# R3-URC18-4-006-001.net
KiCad netlist of a schematic drawn in EAGLE
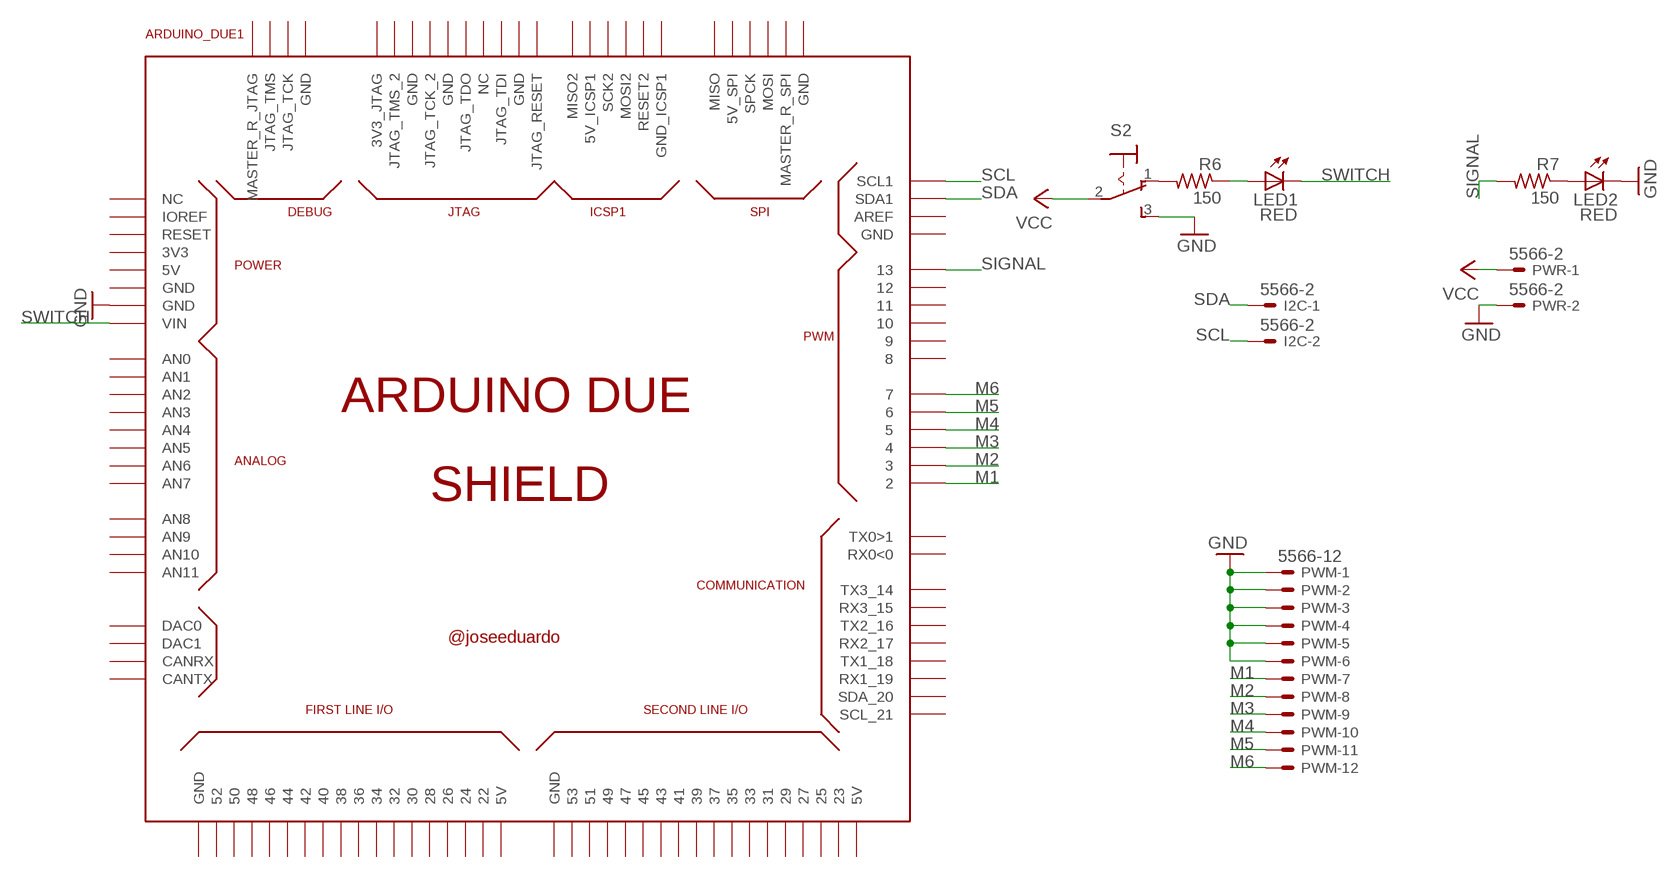
[diagram p0: schematic, sheet 1]

(export (version "E")
  (design (tool "Eeschema 10.0.6"))
  (components
    (comp (ref "ARDUINO_DUE1")
      (value "ARDUINO_DUE_SHIELD")
      (footprint "eagle-import:ARDUINO_DUE_SHIELD")
      (libsource (lib "eagle-import") (part "ARDUINO_DUE_SHIELD"))
    )
    (comp (ref "I2C")
      (value "5566-2")
      (footprint "eagle-import:5566-2")
      (libsource (lib "eagle-import") (part "5566-2"))
    )
    (comp (ref "LED1")
      (value "RED")
      (footprint "eagle-import:LED5MM")
      (libsource (lib "eagle-import") (part "LED5MM"))
    )
    (comp (ref "LED2")
      (value "RED")
      (footprint "eagle-import:LED5MM")
      (libsource (lib "eagle-import") (part "LED5MM"))
    )
    (comp (ref "PWM")
      (value "5566-12")
      (footprint "eagle-import:5566-12")
      (libsource (lib "eagle-import") (part "5566-12"))
    )
    (comp (ref "PWR")
      (value "5566-2")
      (footprint "eagle-import:5566-2")
      (libsource (lib "eagle-import") (part "5566-2"))
    )
    (comp (ref "R6")
      (value "150")
      (footprint "eagle-import:0207_10")
      (libsource (lib "eagle-import") (part "R-US_0207/10"))
    )
    (comp (ref "R7")
      (value "150")
      (footprint "eagle-import:0207_10")
      (libsource (lib "eagle-import") (part "R-US_0207/10"))
    )
    (comp (ref "S2")
      (value "M9040P")
      (footprint "eagle-import:M9040P")
      (libsource (lib "eagle-import") (part "M9040P"))
    )
  )
  (nets
    (net (code "1") (name "/M1") (class "Default")
      (node (ref "ARDUINO_DUE1") (pin "2") (pinfunction "2_2") (pintype "bidirectional"))
      (node (ref "PWM") (pin "7") (pinfunction "S_7") (pintype "passive"))
    )
    (net (code "2") (name "/M2") (class "Default")
      (node (ref "ARDUINO_DUE1") (pin "3") (pinfunction "3_3") (pintype "bidirectional"))
      (node (ref "PWM") (pin "8") (pinfunction "S_8") (pintype "passive"))
    )
    (net (code "3") (name "/M3") (class "Default")
      (node (ref "ARDUINO_DUE1") (pin "4") (pinfunction "4_4") (pintype "bidirectional"))
      (node (ref "PWM") (pin "9") (pinfunction "S_9") (pintype "passive"))
    )
    (net (code "4") (name "/M4") (class "Default")
      (node (ref "ARDUINO_DUE1") (pin "5") (pinfunction "5_5") (pintype "bidirectional"))
      (node (ref "PWM") (pin "10") (pinfunction "S_10") (pintype "passive"))
    )
    (net (code "5") (name "/M5") (class "Default")
      (node (ref "ARDUINO_DUE1") (pin "6") (pinfunction "6_6") (pintype "bidirectional"))
      (node (ref "PWM") (pin "11") (pinfunction "S_11") (pintype "passive"))
    )
    (net (code "6") (name "/M6") (class "Default")
      (node (ref "ARDUINO_DUE1") (pin "7") (pinfunction "7_7") (pintype "bidirectional"))
      (node (ref "PWM") (pin "12") (pinfunction "S_12") (pintype "passive"))
    )
    (net (code "7") (name "/SCL") (class "Default")
      (node (ref "ARDUINO_DUE1") (pin "SCL1") (pinfunction "SCL1_SCL1") (pintype "bidirectional"))
      (node (ref "I2C") (pin "2") (pinfunction "S_2") (pintype "passive"))
    )
    (net (code "8") (name "/SDA") (class "Default")
      (node (ref "ARDUINO_DUE1") (pin "SDA1") (pinfunction "SDA1_SDA1") (pintype "bidirectional"))
      (node (ref "I2C") (pin "1") (pinfunction "S_1") (pintype "passive"))
    )
    (net (code "9") (name "/SIGNAL") (class "Default")
      (node (ref "ARDUINO_DUE1") (pin "13") (pinfunction "13_13") (pintype "bidirectional"))
      (node (ref "R7") (pin "2") (pinfunction "2_2") (pintype "passive"))
    )
    (net (code "10") (name "/SWITCH") (class "Default")
      (node (ref "ARDUINO_DUE1") (pin "VIN") (pinfunction "VIN_VIN") (pintype "bidirectional"))
      (node (ref "LED1") (pin "K") (pinfunction "C_K") (pintype "passive"))
    )
    (net (code "11") (name "GND") (class "Default")
      (node (ref "ARDUINO_DUE1") (pin "GND_1") (pinfunction "GND_GND_1") (pintype "bidirectional"))
      (node (ref "LED2") (pin "K") (pinfunction "C_K") (pintype "passive"))
      (node (ref "PWM") (pin "1") (pinfunction "S_1") (pintype "passive"))
      (node (ref "PWM") (pin "2") (pinfunction "S_2") (pintype "passive"))
      (node (ref "PWM") (pin "3") (pinfunction "S_3") (pintype "passive"))
      (node (ref "PWM") (pin "4") (pinfunction "S_4") (pintype "passive"))
      (node (ref "PWM") (pin "5") (pinfunction "S_5") (pintype "passive"))
      (node (ref "PWM") (pin "6") (pinfunction "S_6") (pintype "passive"))
      (node (ref "PWR") (pin "2") (pinfunction "S_2") (pintype "passive"))
      (node (ref "S2") (pin "3") (pinfunction "S_3") (pintype "passive"))
    )
    (net (code "12") (name "Net-(LED1-PadA)") (class "Default")
      (node (ref "LED1") (pin "A") (pinfunction "A_A") (pintype "passive"))
      (node (ref "R6") (pin "1") (pinfunction "1_1") (pintype "passive"))
    )
    (net (code "13") (name "Net-(LED2-PadA)") (class "Default")
      (node (ref "LED2") (pin "A") (pinfunction "A_A") (pintype "passive"))
      (node (ref "R7") (pin "1") (pinfunction "1_1") (pintype "passive"))
    )
    (net (code "14") (name "Net-(S2-O)") (class "Default")
      (node (ref "R6") (pin "2") (pinfunction "2_2") (pintype "passive"))
      (node (ref "S2") (pin "1") (pinfunction "O_1") (pintype "passive"))
    )
    (net (code "15") (name "VCC") (class "Default")
      (node (ref "PWR") (pin "1") (pinfunction "S_1") (pintype "passive"))
      (node (ref "S2") (pin "2") (pinfunction "P_2") (pintype "passive"))
    )
    (net (code "16") (name "unconnected-(ARDUINO_DUE1-5V-Pad5V0)") (class "Default")
      (node (ref "ARDUINO_DUE1") (pin "5V0") (pinfunction "5V_5V0") (pintype "bidirectional"))
    )
    (net (code "17") (name "unconnected-(ARDUINO_DUE1-5V-Pad5V0_1)") (class "Default")
      (node (ref "ARDUINO_DUE1") (pin "5V0_1") (pinfunction "5V_5V0_1") (pintype "bidirectional"))
    )
    (net (code "18") (name "unconnected-(ARDUINO_DUE1-5V-Pad5V0_2)") (class "Default")
      (node (ref "ARDUINO_DUE1") (pin "5V0_2") (pinfunction "5V_5V0_2") (pintype "bidirectional"))
    )
    (net (code "19") (name "unconnected-(ARDUINO_DUE1-5V_SPI-Pad5V_2)") (class "Default")
      (node (ref "ARDUINO_DUE1") (pin "5V_2") (pinfunction "5V_SPI_5V_2") (pintype "bidirectional"))
    )
    (net (code "20") (name "unconnected-(ARDUINO_DUE1-AN0-PadA0)") (class "Default")
      (node (ref "ARDUINO_DUE1") (pin "A0") (pinfunction "AN0_A0") (pintype "bidirectional"))
    )
    (net (code "21") (name "unconnected-(ARDUINO_DUE1-AN1-PadA1)") (class "Default")
      (node (ref "ARDUINO_DUE1") (pin "A1") (pinfunction "AN1_A1") (pintype "bidirectional"))
    )
    (net (code "22") (name "unconnected-(ARDUINO_DUE1-AN2-PadA2)") (class "Default")
      (node (ref "ARDUINO_DUE1") (pin "A2") (pinfunction "AN2_A2") (pintype "bidirectional"))
    )
    (net (code "23") (name "unconnected-(ARDUINO_DUE1-AN3-PadA3)") (class "Default")
      (node (ref "ARDUINO_DUE1") (pin "A3") (pinfunction "AN3_A3") (pintype "bidirectional"))
    )
    (net (code "24") (name "unconnected-(ARDUINO_DUE1-AN4-PadA4)") (class "Default")
      (node (ref "ARDUINO_DUE1") (pin "A4") (pinfunction "AN4_A4") (pintype "bidirectional"))
    )
    (net (code "25") (name "unconnected-(ARDUINO_DUE1-AN5-PadA5)") (class "Default")
      (node (ref "ARDUINO_DUE1") (pin "A5") (pinfunction "AN5_A5") (pintype "bidirectional"))
    )
    (net (code "26") (name "unconnected-(ARDUINO_DUE1-AN6-PadA6)") (class "Default")
      (node (ref "ARDUINO_DUE1") (pin "A6") (pinfunction "AN6_A6") (pintype "bidirectional"))
    )
    (net (code "27") (name "unconnected-(ARDUINO_DUE1-AN7-PadA7)") (class "Default")
      (node (ref "ARDUINO_DUE1") (pin "A7") (pinfunction "AN7_A7") (pintype "bidirectional"))
    )
    (net (code "28") (name "unconnected-(ARDUINO_DUE1-AN8-PadA8)") (class "Default")
      (node (ref "ARDUINO_DUE1") (pin "A8") (pinfunction "AN8_A8") (pintype "bidirectional"))
    )
    (net (code "29") (name "unconnected-(ARDUINO_DUE1-AN9-PadA9)") (class "Default")
      (node (ref "ARDUINO_DUE1") (pin "A9") (pinfunction "AN9_A9") (pintype "bidirectional"))
    )
    (net (code "30") (name "unconnected-(ARDUINO_DUE1-AN10-PadA10)") (class "Default")
      (node (ref "ARDUINO_DUE1") (pin "A10") (pinfunction "AN10_A10") (pintype "bidirectional"))
    )
    (net (code "31") (name "unconnected-(ARDUINO_DUE1-AN11-PadA11)") (class "Default")
      (node (ref "ARDUINO_DUE1") (pin "A11") (pinfunction "AN11_A11") (pintype "bidirectional"))
    )
    (net (code "32") (name "unconnected-(ARDUINO_DUE1-GND-PadGND_2)") (class "Default")
      (node (ref "ARDUINO_DUE1") (pin "GND_2") (pinfunction "GND_GND_2") (pintype "bidirectional"))
    )
    (net (code "33") (name "unconnected-(ARDUINO_DUE1-GND-PadGND_3)") (class "Default")
      (node (ref "ARDUINO_DUE1") (pin "GND_3") (pinfunction "GND_GND_3") (pintype "bidirectional"))
    )
    (net (code "34") (name "unconnected-(ARDUINO_DUE1-GND-PadGND_4)") (class "Default")
      (node (ref "ARDUINO_DUE1") (pin "GND_4") (pinfunction "GND_GND_4") (pintype "bidirectional"))
    )
    (net (code "35") (name "unconnected-(ARDUINO_DUE1-GND-PadGND_5)") (class "Default")
      (node (ref "ARDUINO_DUE1") (pin "GND_5") (pinfunction "GND_GND_5") (pintype "bidirectional"))
    )
    (net (code "36") (name "unconnected-(ARDUINO_DUE1-GND-PadGND_7)") (class "Default")
      (node (ref "ARDUINO_DUE1") (pin "GND_7") (pinfunction "GND_GND_7") (pintype "bidirectional"))
    )
    (net (code "37") (name "unconnected-(ARDUINO_DUE1-GND-PadGND_8)") (class "Default")
      (node (ref "ARDUINO_DUE1") (pin "GND_8") (pinfunction "GND_GND_8") (pintype "bidirectional"))
    )
    (net (code "38") (name "unconnected-(ARDUINO_DUE1-GND-PadGND_9)") (class "Default")
      (node (ref "ARDUINO_DUE1") (pin "GND_9") (pinfunction "GND_GND_9") (pintype "bidirectional"))
    )
    (net (code "39") (name "unconnected-(ARDUINO_DUE1-GND-PadGND_10)") (class "Default")
      (node (ref "ARDUINO_DUE1") (pin "GND_10") (pinfunction "GND_GND_10") (pintype "bidirectional"))
    )
    (net (code "40") (name "unconnected-(ARDUINO_DUE1-MASTER_R_JTAG-PadMASTER_RESET_JTAG)") (class "Default")
      (node (ref "ARDUINO_DUE1") (pin "MASTER_RESET_JTAG") (pinfunction "MASTER_R_JTAG_MASTER_RESET_JTAG") (pintype "bidirectional"))
    )
    (net (code "41") (name "unconnected-(ARDUINO_DUE1-MASTER_R_SPI-PadMASTER_RESET_SPI)") (class "Default")
      (node (ref "ARDUINO_DUE1") (pin "MASTER_RESET_SPI") (pinfunction "MASTER_R_SPI_MASTER_RESET_SPI") (pintype "bidirectional"))
    )
    (net (code "42") (name "unconnected-(ARDUINO_DUE1-NC-PadNC_2)") (class "Default")
      (node (ref "ARDUINO_DUE1") (pin "NC_2") (pinfunction "NC_NC_2") (pintype "no_connect"))
    )
    (net (code "43") (name "unconnected-(ARDUINO_DUE1-NC-PadNC_5)") (class "Default")
      (node (ref "ARDUINO_DUE1") (pin "NC_5") (pinfunction "NC_NC_5") (pintype "bidirectional"))
    )
    (net (code "44") (name "unconnected-(ARDUINO_DUE1-Pad3V3)") (class "Default")
      (node (ref "ARDUINO_DUE1") (pin "3V3") (pinfunction "3V3_3V3") (pintype "bidirectional"))
    )
    (net (code "45") (name "unconnected-(ARDUINO_DUE1-Pad3V3_JTAG)") (class "Default")
      (node (ref "ARDUINO_DUE1") (pin "3V3_JTAG") (pinfunction "3V3_JTAG_3V3_JTAG") (pintype "bidirectional"))
    )
    (net (code "46") (name "unconnected-(ARDUINO_DUE1-Pad5V_ICSP1)") (class "Default")
      (node (ref "ARDUINO_DUE1") (pin "5V_ICSP1") (pinfunction "5V_ICSP1_5V_ICSP1") (pintype "bidirectional"))
    )
    (net (code "47") (name "unconnected-(ARDUINO_DUE1-Pad8)") (class "Default")
      (node (ref "ARDUINO_DUE1") (pin "8") (pinfunction "8_8") (pintype "bidirectional"))
    )
    (net (code "48") (name "unconnected-(ARDUINO_DUE1-Pad9)") (class "Default")
      (node (ref "ARDUINO_DUE1") (pin "9") (pinfunction "9_9") (pintype "bidirectional"))
    )
    (net (code "49") (name "unconnected-(ARDUINO_DUE1-Pad10)") (class "Default")
      (node (ref "ARDUINO_DUE1") (pin "10") (pinfunction "10_10") (pintype "bidirectional"))
    )
    (net (code "50") (name "unconnected-(ARDUINO_DUE1-Pad11)") (class "Default")
      (node (ref "ARDUINO_DUE1") (pin "11") (pinfunction "11_11") (pintype "bidirectional"))
    )
    (net (code "51") (name "unconnected-(ARDUINO_DUE1-Pad12)") (class "Default")
      (node (ref "ARDUINO_DUE1") (pin "12") (pinfunction "12_12") (pintype "bidirectional"))
    )
    (net (code "52") (name "unconnected-(ARDUINO_DUE1-Pad22)") (class "Default")
      (node (ref "ARDUINO_DUE1") (pin "22") (pinfunction "22_22") (pintype "bidirectional"))
    )
    (net (code "53") (name "unconnected-(ARDUINO_DUE1-Pad23)") (class "Default")
      (node (ref "ARDUINO_DUE1") (pin "23") (pinfunction "23_23") (pintype "bidirectional"))
    )
    (net (code "54") (name "unconnected-(ARDUINO_DUE1-Pad24)") (class "Default")
      (node (ref "ARDUINO_DUE1") (pin "24") (pinfunction "24_24") (pintype "bidirectional"))
    )
    (net (code "55") (name "unconnected-(ARDUINO_DUE1-Pad25)") (class "Default")
      (node (ref "ARDUINO_DUE1") (pin "25") (pinfunction "25_25") (pintype "bidirectional"))
    )
    (net (code "56") (name "unconnected-(ARDUINO_DUE1-Pad26)") (class "Default")
      (node (ref "ARDUINO_DUE1") (pin "26") (pinfunction "26_26") (pintype "bidirectional"))
    )
    (net (code "57") (name "unconnected-(ARDUINO_DUE1-Pad27)") (class "Default")
      (node (ref "ARDUINO_DUE1") (pin "27") (pinfunction "27_27") (pintype "bidirectional"))
    )
    (net (code "58") (name "unconnected-(ARDUINO_DUE1-Pad28)") (class "Default")
      (node (ref "ARDUINO_DUE1") (pin "28") (pinfunction "28_28") (pintype "bidirectional"))
    )
    (net (code "59") (name "unconnected-(ARDUINO_DUE1-Pad29)") (class "Default")
      (node (ref "ARDUINO_DUE1") (pin "29") (pinfunction "29_29") (pintype "bidirectional"))
    )
    (net (code "60") (name "unconnected-(ARDUINO_DUE1-Pad30)") (class "Default")
      (node (ref "ARDUINO_DUE1") (pin "30") (pinfunction "30_30") (pintype "bidirectional"))
    )
    (net (code "61") (name "unconnected-(ARDUINO_DUE1-Pad31)") (class "Default")
      (node (ref "ARDUINO_DUE1") (pin "31") (pinfunction "31_31") (pintype "bidirectional"))
    )
    (net (code "62") (name "unconnected-(ARDUINO_DUE1-Pad32)") (class "Default")
      (node (ref "ARDUINO_DUE1") (pin "32") (pinfunction "32_32") (pintype "bidirectional"))
    )
    (net (code "63") (name "unconnected-(ARDUINO_DUE1-Pad33)") (class "Default")
      (node (ref "ARDUINO_DUE1") (pin "33") (pinfunction "33_33") (pintype "bidirectional"))
    )
    (net (code "64") (name "unconnected-(ARDUINO_DUE1-Pad34)") (class "Default")
      (node (ref "ARDUINO_DUE1") (pin "34") (pinfunction "34_34") (pintype "bidirectional"))
    )
    (net (code "65") (name "unconnected-(ARDUINO_DUE1-Pad35)") (class "Default")
      (node (ref "ARDUINO_DUE1") (pin "35") (pinfunction "35_35") (pintype "bidirectional"))
    )
    (net (code "66") (name "unconnected-(ARDUINO_DUE1-Pad36)") (class "Default")
      (node (ref "ARDUINO_DUE1") (pin "36") (pinfunction "36_36") (pintype "bidirectional"))
    )
    (net (code "67") (name "unconnected-(ARDUINO_DUE1-Pad37)") (class "Default")
      (node (ref "ARDUINO_DUE1") (pin "37") (pinfunction "37_37") (pintype "bidirectional"))
    )
    (net (code "68") (name "unconnected-(ARDUINO_DUE1-Pad38)") (class "Default")
      (node (ref "ARDUINO_DUE1") (pin "38") (pinfunction "38_38") (pintype "bidirectional"))
    )
    (net (code "69") (name "unconnected-(ARDUINO_DUE1-Pad39)") (class "Default")
      (node (ref "ARDUINO_DUE1") (pin "39") (pinfunction "39_39") (pintype "bidirectional"))
    )
    (net (code "70") (name "unconnected-(ARDUINO_DUE1-Pad40)") (class "Default")
      (node (ref "ARDUINO_DUE1") (pin "40") (pinfunction "40_40") (pintype "bidirectional"))
    )
    (net (code "71") (name "unconnected-(ARDUINO_DUE1-Pad41)") (class "Default")
      (node (ref "ARDUINO_DUE1") (pin "41") (pinfunction "41_41") (pintype "bidirectional"))
    )
    (net (code "72") (name "unconnected-(ARDUINO_DUE1-Pad42)") (class "Default")
      (node (ref "ARDUINO_DUE1") (pin "42") (pinfunction "42_42") (pintype "bidirectional"))
    )
    (net (code "73") (name "unconnected-(ARDUINO_DUE1-Pad43)") (class "Default")
      (node (ref "ARDUINO_DUE1") (pin "43") (pinfunction "43_43") (pintype "bidirectional"))
    )
    (net (code "74") (name "unconnected-(ARDUINO_DUE1-Pad44)") (class "Default")
      (node (ref "ARDUINO_DUE1") (pin "44") (pinfunction "44_44") (pintype "bidirectional"))
    )
    (net (code "75") (name "unconnected-(ARDUINO_DUE1-Pad45)") (class "Default")
      (node (ref "ARDUINO_DUE1") (pin "45") (pinfunction "45_45") (pintype "bidirectional"))
    )
    (net (code "76") (name "unconnected-(ARDUINO_DUE1-Pad46)") (class "Default")
      (node (ref "ARDUINO_DUE1") (pin "46") (pinfunction "46_46") (pintype "bidirectional"))
    )
    (net (code "77") (name "unconnected-(ARDUINO_DUE1-Pad47)") (class "Default")
      (node (ref "ARDUINO_DUE1") (pin "47") (pinfunction "47_47") (pintype "bidirectional"))
    )
    (net (code "78") (name "unconnected-(ARDUINO_DUE1-Pad48)") (class "Default")
      (node (ref "ARDUINO_DUE1") (pin "48") (pinfunction "48_48") (pintype "bidirectional"))
    )
    (net (code "79") (name "unconnected-(ARDUINO_DUE1-Pad49)") (class "Default")
      (node (ref "ARDUINO_DUE1") (pin "49") (pinfunction "49_49") (pintype "bidirectional"))
    )
    (net (code "80") (name "unconnected-(ARDUINO_DUE1-Pad50)") (class "Default")
      (node (ref "ARDUINO_DUE1") (pin "50") (pinfunction "50_50") (pintype "bidirectional"))
    )
    (net (code "81") (name "unconnected-(ARDUINO_DUE1-Pad51)") (class "Default")
      (node (ref "ARDUINO_DUE1") (pin "51") (pinfunction "51_51") (pintype "bidirectional"))
    )
    (net (code "82") (name "unconnected-(ARDUINO_DUE1-Pad52)") (class "Default")
      (node (ref "ARDUINO_DUE1") (pin "52") (pinfunction "52_52") (pintype "bidirectional"))
    )
    (net (code "83") (name "unconnected-(ARDUINO_DUE1-Pad53)") (class "Default")
      (node (ref "ARDUINO_DUE1") (pin "53") (pinfunction "53_53") (pintype "bidirectional"))
    )
    (net (code "84") (name "unconnected-(ARDUINO_DUE1-PadAREF)") (class "Default")
      (node (ref "ARDUINO_DUE1") (pin "AREF") (pinfunction "AREF_AREF") (pintype "bidirectional"))
    )
    (net (code "85") (name "unconnected-(ARDUINO_DUE1-PadCANRX)") (class "Default")
      (node (ref "ARDUINO_DUE1") (pin "CANRX") (pinfunction "CANRX_CANRX") (pintype "bidirectional"))
    )
    (net (code "86") (name "unconnected-(ARDUINO_DUE1-PadCANTX)") (class "Default")
      (node (ref "ARDUINO_DUE1") (pin "CANTX") (pinfunction "CANTX_CANTX") (pintype "bidirectional"))
    )
    (net (code "87") (name "unconnected-(ARDUINO_DUE1-PadDAC0)") (class "Default")
      (node (ref "ARDUINO_DUE1") (pin "DAC0") (pinfunction "DAC0_DAC0") (pintype "bidirectional"))
    )
    (net (code "88") (name "unconnected-(ARDUINO_DUE1-PadDAC1)") (class "Default")
      (node (ref "ARDUINO_DUE1") (pin "DAC1") (pinfunction "DAC1_DAC1") (pintype "bidirectional"))
    )
    (net (code "89") (name "unconnected-(ARDUINO_DUE1-PadGND)") (class "Default")
      (node (ref "ARDUINO_DUE1") (pin "GND") (pinfunction "GND_GND") (pintype "bidirectional"))
    )
    (net (code "90") (name "unconnected-(ARDUINO_DUE1-PadGND_ICSP1)") (class "Default")
      (node (ref "ARDUINO_DUE1") (pin "GND_ICSP1") (pinfunction "GND_ICSP1_GND_ICSP1") (pintype "bidirectional"))
    )
    (net (code "91") (name "unconnected-(ARDUINO_DUE1-PadIOREF)") (class "Default")
      (node (ref "ARDUINO_DUE1") (pin "IOREF") (pinfunction "IOREF_IOREF") (pintype "bidirectional"))
    )
    (net (code "92") (name "unconnected-(ARDUINO_DUE1-PadJTAG_RESET)") (class "Default")
      (node (ref "ARDUINO_DUE1") (pin "JTAG_RESET") (pinfunction "JTAG_RESET_JTAG_RESET") (pintype "bidirectional"))
    )
    (net (code "93") (name "unconnected-(ARDUINO_DUE1-PadJTAG_TCK)") (class "Default")
      (node (ref "ARDUINO_DUE1") (pin "JTAG_TCK") (pinfunction "JTAG_TCK_JTAG_TCK") (pintype "bidirectional"))
    )
    (net (code "94") (name "unconnected-(ARDUINO_DUE1-PadJTAG_TCK_2)") (class "Default")
      (node (ref "ARDUINO_DUE1") (pin "JTAG_TCK_2") (pinfunction "JTAG_TCK_2_JTAG_TCK_2") (pintype "bidirectional"))
    )
    (net (code "95") (name "unconnected-(ARDUINO_DUE1-PadJTAG_TDI)") (class "Default")
      (node (ref "ARDUINO_DUE1") (pin "JTAG_TDI") (pinfunction "JTAG_TDI_JTAG_TDI") (pintype "bidirectional"))
    )
    (net (code "96") (name "unconnected-(ARDUINO_DUE1-PadJTAG_TDO)") (class "Default")
      (node (ref "ARDUINO_DUE1") (pin "JTAG_TDO") (pinfunction "JTAG_TDO_JTAG_TDO") (pintype "bidirectional"))
    )
    (net (code "97") (name "unconnected-(ARDUINO_DUE1-PadJTAG_TMS)") (class "Default")
      (node (ref "ARDUINO_DUE1") (pin "JTAG_TMS") (pinfunction "JTAG_TMS_JTAG_TMS") (pintype "bidirectional"))
    )
    (net (code "98") (name "unconnected-(ARDUINO_DUE1-PadJTAG_TMS_2)") (class "Default")
      (node (ref "ARDUINO_DUE1") (pin "JTAG_TMS_2") (pinfunction "JTAG_TMS_2_JTAG_TMS_2") (pintype "bidirectional"))
    )
    (net (code "99") (name "unconnected-(ARDUINO_DUE1-PadMISO)") (class "Default")
      (node (ref "ARDUINO_DUE1") (pin "MISO") (pinfunction "MISO_MISO") (pintype "bidirectional"))
    )
    (net (code "100") (name "unconnected-(ARDUINO_DUE1-PadMISO2)") (class "Default")
      (node (ref "ARDUINO_DUE1") (pin "MISO2") (pinfunction "MISO2_MISO2") (pintype "bidirectional"))
    )
    (net (code "101") (name "unconnected-(ARDUINO_DUE1-PadMOSI)") (class "Default")
      (node (ref "ARDUINO_DUE1") (pin "MOSI") (pinfunction "MOSI_MOSI") (pintype "bidirectional"))
    )
    (net (code "102") (name "unconnected-(ARDUINO_DUE1-PadMOSI2)") (class "Default")
      (node (ref "ARDUINO_DUE1") (pin "MOSI2") (pinfunction "MOSI2_MOSI2") (pintype "bidirectional"))
    )
    (net (code "103") (name "unconnected-(ARDUINO_DUE1-PadRESET)") (class "Default")
      (node (ref "ARDUINO_DUE1") (pin "RESET") (pinfunction "RESET_RESET") (pintype "bidirectional"))
    )
    (net (code "104") (name "unconnected-(ARDUINO_DUE1-PadRESET2)") (class "Default")
      (node (ref "ARDUINO_DUE1") (pin "RESET2") (pinfunction "RESET2_RESET2") (pintype "bidirectional"))
    )
    (net (code "105") (name "unconnected-(ARDUINO_DUE1-PadSCK2)") (class "Default")
      (node (ref "ARDUINO_DUE1") (pin "SCK2") (pinfunction "SCK2_SCK2") (pintype "bidirectional"))
    )
    (net (code "106") (name "unconnected-(ARDUINO_DUE1-PadSPCK)") (class "Default")
      (node (ref "ARDUINO_DUE1") (pin "SPCK") (pinfunction "SPCK_SPCK") (pintype "bidirectional"))
    )
    (net (code "107") (name "unconnected-(ARDUINO_DUE1-RX0<0-Pad0)") (class "Default")
      (node (ref "ARDUINO_DUE1") (pin "0") (pinfunction "RX0<0_0") (pintype "bidirectional"))
    )
    (net (code "108") (name "unconnected-(ARDUINO_DUE1-RX1_19-Pad19)") (class "Default")
      (node (ref "ARDUINO_DUE1") (pin "19") (pinfunction "RX1_19_19") (pintype "bidirectional"))
    )
    (net (code "109") (name "unconnected-(ARDUINO_DUE1-RX2_17-Pad17)") (class "Default")
      (node (ref "ARDUINO_DUE1") (pin "17") (pinfunction "RX2_17_17") (pintype "bidirectional"))
    )
    (net (code "110") (name "unconnected-(ARDUINO_DUE1-RX3_15-Pad15)") (class "Default")
      (node (ref "ARDUINO_DUE1") (pin "15") (pinfunction "RX3_15_15") (pintype "bidirectional"))
    )
    (net (code "111") (name "unconnected-(ARDUINO_DUE1-SCL_21-Pad21)") (class "Default")
      (node (ref "ARDUINO_DUE1") (pin "21") (pinfunction "SCL_21_21") (pintype "bidirectional"))
    )
    (net (code "112") (name "unconnected-(ARDUINO_DUE1-SDA_20-Pad20)") (class "Default")
      (node (ref "ARDUINO_DUE1") (pin "20") (pinfunction "SDA_20_20") (pintype "bidirectional"))
    )
    (net (code "113") (name "unconnected-(ARDUINO_DUE1-TX0>1-Pad1)") (class "Default")
      (node (ref "ARDUINO_DUE1") (pin "1") (pinfunction "TX0>1_1") (pintype "bidirectional"))
    )
    (net (code "114") (name "unconnected-(ARDUINO_DUE1-TX1_18-Pad18)") (class "Default")
      (node (ref "ARDUINO_DUE1") (pin "18") (pinfunction "TX1_18_18") (pintype "bidirectional"))
    )
    (net (code "115") (name "unconnected-(ARDUINO_DUE1-TX2_16-Pad16)") (class "Default")
      (node (ref "ARDUINO_DUE1") (pin "16") (pinfunction "TX2_16_16") (pintype "bidirectional"))
    )
    (net (code "116") (name "unconnected-(ARDUINO_DUE1-TX3_14-Pad14)") (class "Default")
      (node (ref "ARDUINO_DUE1") (pin "14") (pinfunction "TX3_14_14") (pintype "bidirectional"))
    )
  )
)
